# TRV_W5200.net
KiCad netlist of a schematic drawn in EAGLE
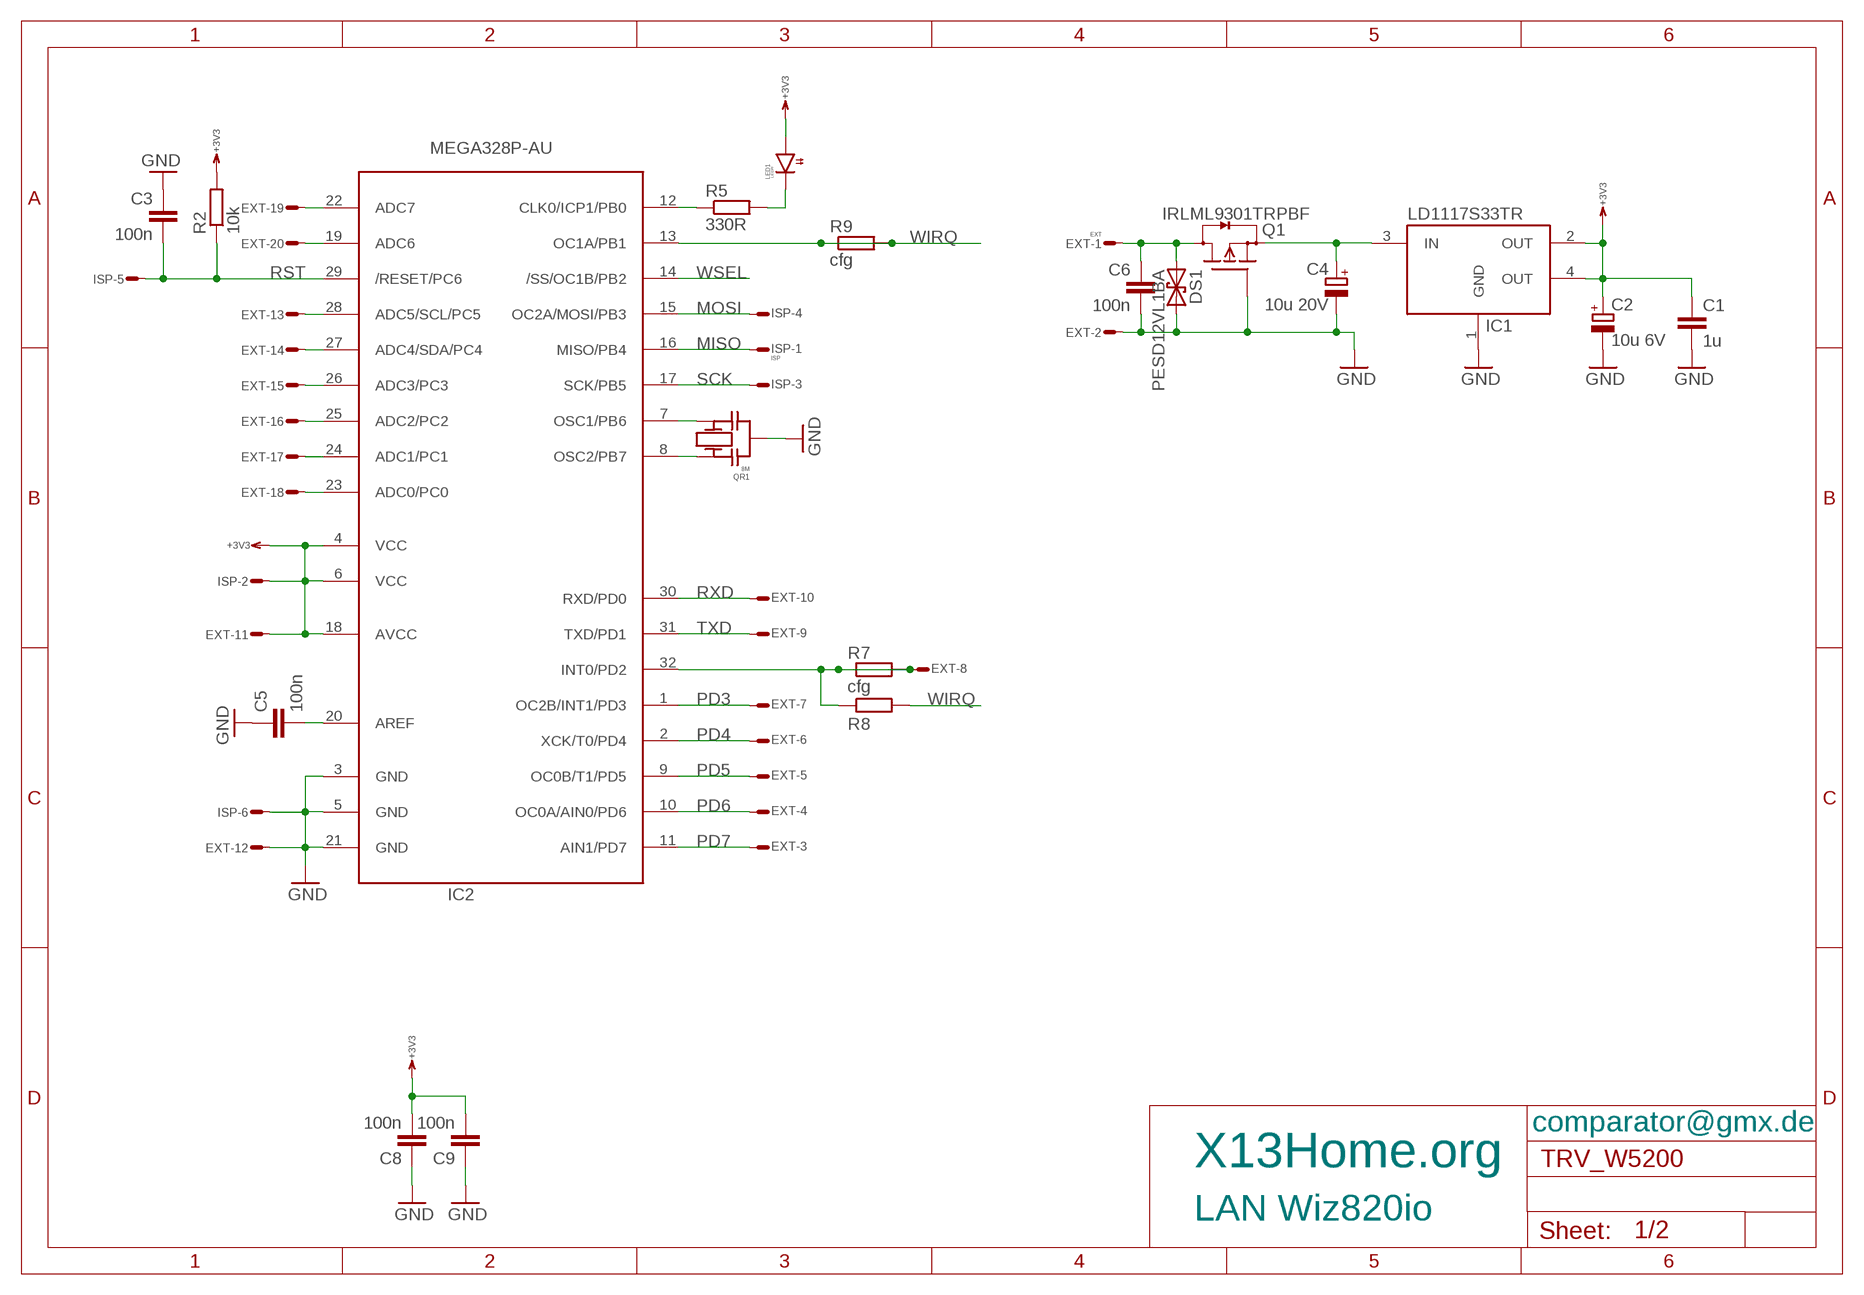
[diagram p0: schematic, sheet 1]
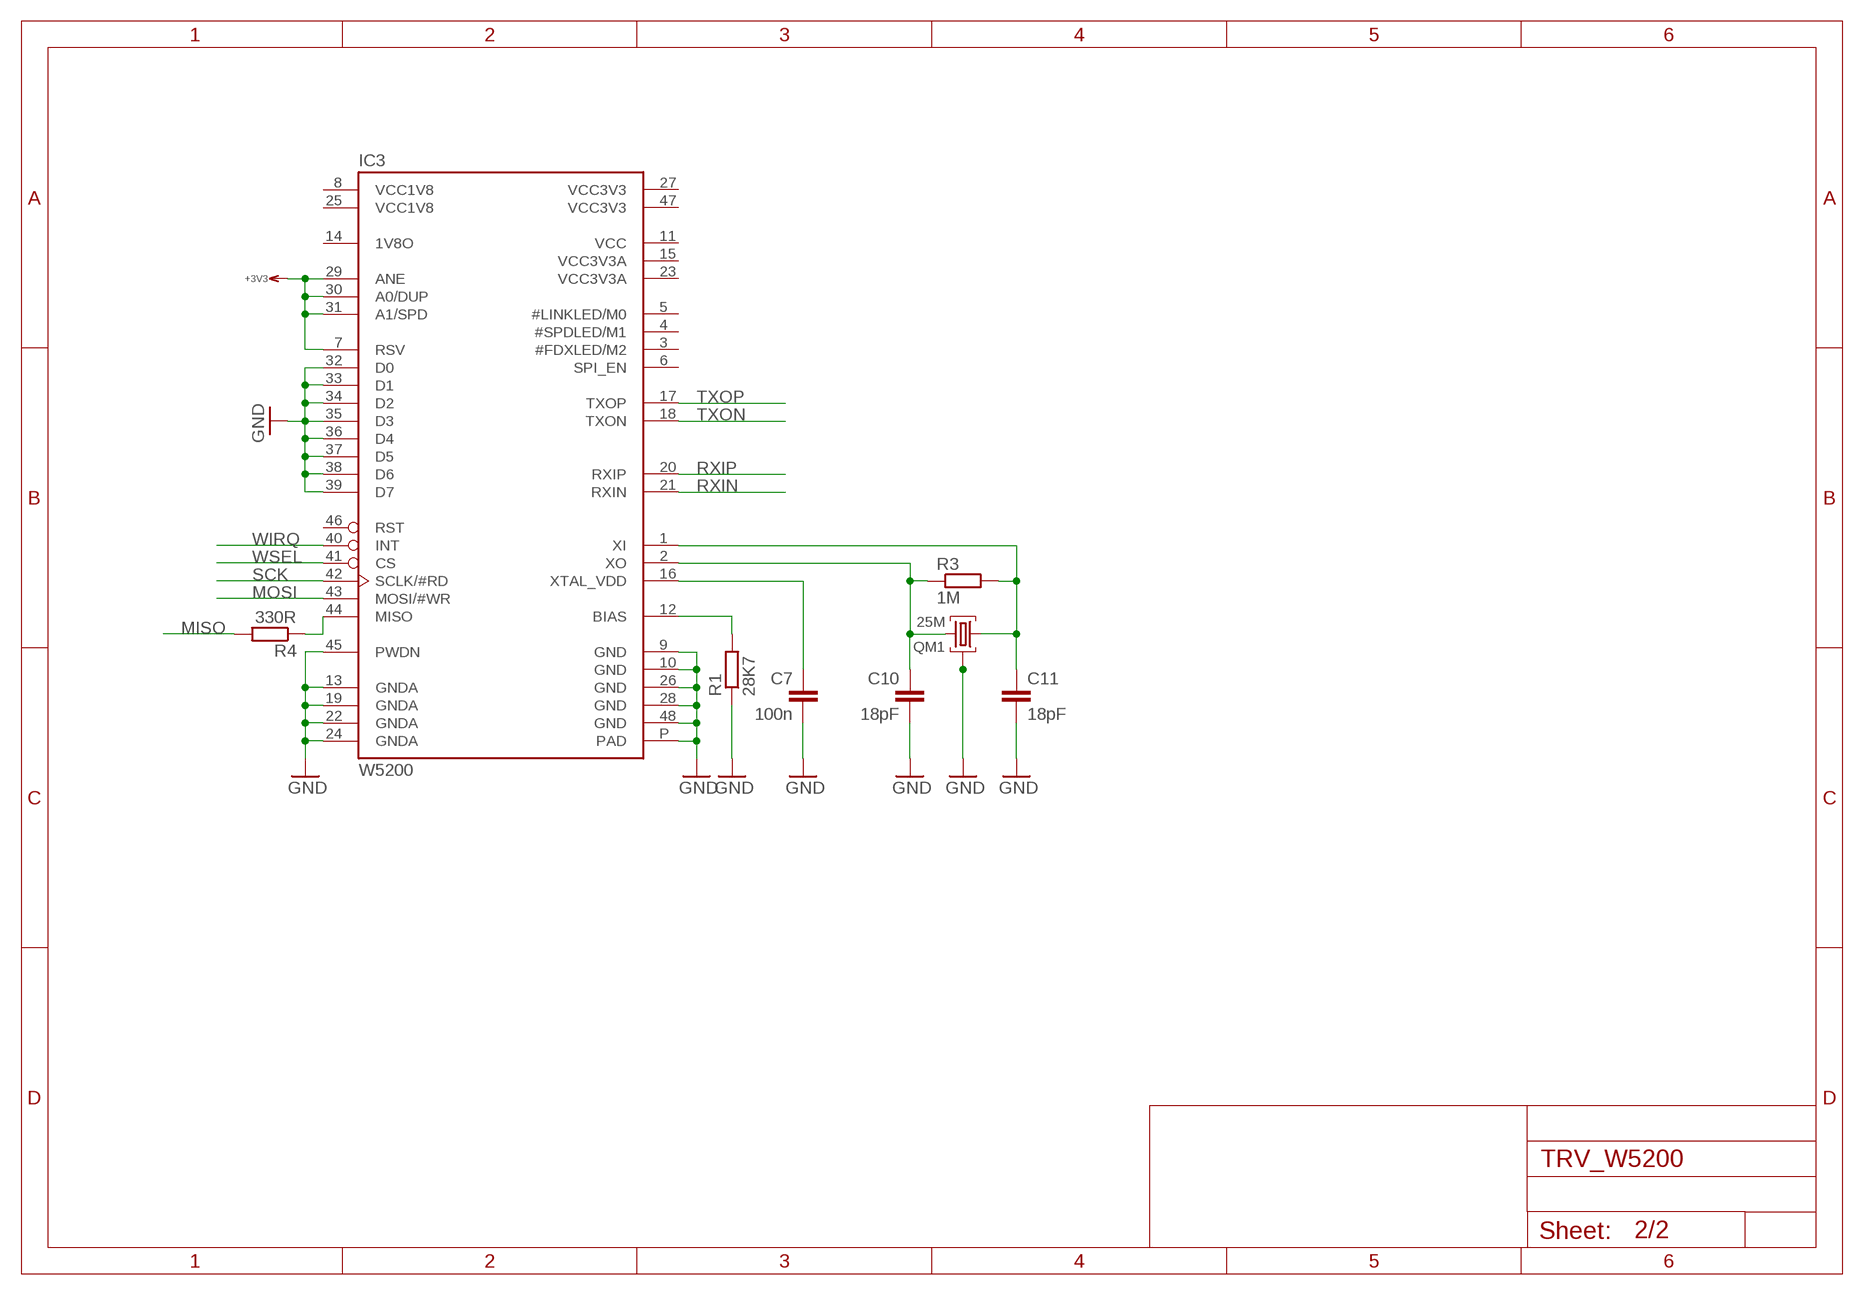
[diagram p1: schematic, sheet 2]

(export (version "E")
  (design (tool "Eeschema 10.0.6"))
  (components
    (comp (ref "C1")
      (value "1u")
      (footprint "eagle-import:0603")
      (libsource (lib "eagle-import") (part "C0603"))
    )
    (comp (ref "C2")
      (value "10u 6V")
      (footprint "eagle-import:SMC_A")
      (libsource (lib "eagle-import") (part "C_POLSMCA"))
    )
    (comp (ref "C3")
      (value "100n")
      (footprint "eagle-import:0603")
      (libsource (lib "eagle-import") (part "C0603"))
    )
    (comp (ref "C4")
      (value "10u 20V")
      (footprint "eagle-import:SMC_B")
      (libsource (lib "eagle-import") (part "C_POLSMCB"))
    )
    (comp (ref "C5")
      (value "100n")
      (footprint "eagle-import:0603")
      (libsource (lib "eagle-import") (part "C0603"))
    )
    (comp (ref "C6")
      (value "100n")
      (footprint "eagle-import:0603")
      (libsource (lib "eagle-import") (part "C0603"))
    )
    (comp (ref "C8")
      (value "100n")
      (footprint "eagle-import:0603")
      (libsource (lib "eagle-import") (part "C0603"))
    )
    (comp (ref "C9")
      (value "100n")
      (footprint "eagle-import:0603")
      (libsource (lib "eagle-import") (part "C0603"))
    )
    (comp (ref "DS1")
      (value "PESD12VL1BA")
      (footprint "eagle-import:SOD323")
      (libsource (lib "eagle-import") (part "TVS-U323"))
    )
    (comp (ref "EXT")
      (value "EXT")
      (footprint "eagle-import:ML20S")
      (libsource (lib "eagle-import") (part "ML20?ES"))
    )
    (comp (ref "IC1")
      (value "LD1117S33TR")
      (footprint "eagle-import:SOT223")
      (libsource (lib "eagle-import") (part "LDO_4P"))
    )
    (comp (ref "IC2")
      (value "MEGA328P-AU")
      (footprint "eagle-import:TQFP32-08")
      (libsource (lib "eagle-import") (part "MEGA168PA"))
    )
    (comp (ref "ISP")
      (value "ISP")
      (footprint "eagle-import:ML6S")
      (libsource (lib "eagle-import") (part "ML6ES"))
    )
    (comp (ref "LED1")
      (value "LEDR")
      (footprint "eagle-import:T1-3_4")
      (libsource (lib "eagle-import") (part "LEDT134"))
    )
    (comp (ref "Q1")
      (value "IRLML9301TRPBF")
      (footprint "eagle-import:SOT23")
      (libsource (lib "eagle-import") (part "FET-PDSOT23"))
    )
    (comp (ref "QR1")
      (value "8M")
      (footprint "eagle-import:CSTCE")
      (libsource (lib "eagle-import") (part "QRCE"))
    )
    (comp (ref "R2")
      (value "10k")
      (footprint "eagle-import:0603")
      (libsource (lib "eagle-import") (part "R0603"))
    )
    (comp (ref "R5")
      (value "330R")
      (footprint "eagle-import:0603")
      (libsource (lib "eagle-import") (part "R0603"))
    )
    (comp (ref "R7")
      (value "cfg")
      (footprint "eagle-import:0402")
      (libsource (lib "eagle-import") (part "R0402"))
    )
    (comp (ref "R8")
      (value "cfg")
      (footprint "eagle-import:0402")
      (libsource (lib "eagle-import") (part "R0402"))
    )
    (comp (ref "R9")
      (value "cfg")
      (footprint "eagle-import:0402")
      (libsource (lib "eagle-import") (part "R0402"))
    )
    (comp (ref "C7")
      (value "100n")
      (footprint "eagle-import:0603")
      (libsource (lib "eagle-import") (part "C0603"))
    )
    (comp (ref "C10")
      (value "18pF")
      (footprint "eagle-import:0603")
      (libsource (lib "eagle-import") (part "C0603"))
    )
    (comp (ref "C11")
      (value "18pF")
      (footprint "eagle-import:0603")
      (libsource (lib "eagle-import") (part "C0603"))
    )
    (comp (ref "IC3")
      (value "W5200")
      (footprint "eagle-import:QFN48")
      (libsource (lib "eagle-import") (part "W5200"))
    )
    (comp (ref "QM1")
      (value "25M")
      (footprint "eagle-import:SMD_4P_3.2X2.5")
      (libsource (lib "eagle-import") (part "QM3.2X2.5"))
    )
    (comp (ref "R1")
      (value "28K7")
      (footprint "eagle-import:0603")
      (libsource (lib "eagle-import") (part "R0603"))
    )
    (comp (ref "R3")
      (value "1M")
      (footprint "eagle-import:0603")
      (libsource (lib "eagle-import") (part "R0603"))
    )
    (comp (ref "R4")
      (value "330R")
      (footprint "eagle-import:0603")
      (libsource (lib "eagle-import") (part "R0603"))
    )
  )
  (nets
    (net (code "1") (name "+3V3") (class "Default")
      (node (ref "C1") (pin "1") (pinfunction "1_1") (pintype "passive"))
      (node (ref "C2") (pin "+") (pinfunction "+_+") (pintype "passive"))
      (node (ref "C8") (pin "2") (pinfunction "2_2") (pintype "passive"))
      (node (ref "C9") (pin "2") (pinfunction "2_2") (pintype "passive"))
      (node (ref "EXT") (pin "11") (pinfunction "S_11") (pintype "passive"))
      (node (ref "IC1") (pin "2") (pinfunction "OUT_2") (pintype "bidirectional"))
      (node (ref "IC1") (pin "4") (pinfunction "OUT_4") (pintype "bidirectional"))
      (node (ref "IC2") (pin "18") (pinfunction "AVCC_18") (pintype "bidirectional"))
      (node (ref "IC2") (pin "4") (pinfunction "VCC_4") (pintype "bidirectional"))
      (node (ref "IC2") (pin "6") (pinfunction "VCC_6") (pintype "bidirectional"))
      (node (ref "IC3") (pin "29") (pinfunction "ANE_29") (pintype "input"))
      (node (ref "IC3") (pin "30") (pinfunction "A0/DUP_30") (pintype "input"))
      (node (ref "IC3") (pin "31") (pinfunction "A1/SPD_31") (pintype "input"))
      (node (ref "IC3") (pin "7") (pinfunction "RSV_7") (pintype "input"))
      (node (ref "ISP") (pin "2") (pinfunction "S_2") (pintype "passive"))
      (node (ref "LED1") (pin "A") (pinfunction "A_A") (pintype "bidirectional"))
      (node (ref "R2") (pin "2") (pinfunction "2_2") (pintype "passive"))
    )
    (net (code "2") (name "GND") (class "Default")
      (node (ref "C1") (pin "2") (pinfunction "2_2") (pintype "passive"))
      (node (ref "C10") (pin "2") (pinfunction "2_2") (pintype "passive"))
      (node (ref "C11") (pin "2") (pinfunction "2_2") (pintype "passive"))
      (node (ref "C2") (pin "-") (pinfunction "-_-") (pintype "passive"))
      (node (ref "C3") (pin "1") (pinfunction "1_1") (pintype "passive"))
      (node (ref "C4") (pin "-") (pinfunction "-_-") (pintype "passive"))
      (node (ref "C5") (pin "1") (pinfunction "1_1") (pintype "passive"))
      (node (ref "C6") (pin "2") (pinfunction "2_2") (pintype "passive"))
      (node (ref "C7") (pin "2") (pinfunction "2_2") (pintype "passive"))
      (node (ref "C8") (pin "1") (pinfunction "1_1") (pintype "passive"))
      (node (ref "C9") (pin "1") (pinfunction "1_1") (pintype "passive"))
      (node (ref "DS1") (pin "C") (pinfunction "2_C") (pintype "passive"))
      (node (ref "EXT") (pin "12") (pinfunction "S_12") (pintype "passive"))
      (node (ref "EXT") (pin "2") (pinfunction "S_2") (pintype "passive"))
      (node (ref "IC1") (pin "1") (pinfunction "GND_1") (pintype "bidirectional"))
      (node (ref "IC2") (pin "21") (pinfunction "GND_21") (pintype "bidirectional"))
      (node (ref "IC2") (pin "3") (pinfunction "GND_3") (pintype "bidirectional"))
      (node (ref "IC2") (pin "5") (pinfunction "GND_5") (pintype "bidirectional"))
      (node (ref "IC3") (pin "10") (pinfunction "GND_10") (pintype "bidirectional"))
      (node (ref "IC3") (pin "13") (pinfunction "GNDA_13") (pintype "bidirectional"))
      (node (ref "IC3") (pin "19") (pinfunction "GNDA_19") (pintype "bidirectional"))
      (node (ref "IC3") (pin "22") (pinfunction "GNDA_22") (pintype "bidirectional"))
      (node (ref "IC3") (pin "24") (pinfunction "GNDA_24") (pintype "bidirectional"))
      (node (ref "IC3") (pin "26") (pinfunction "GND_26") (pintype "bidirectional"))
      (node (ref "IC3") (pin "28") (pinfunction "GND_28") (pintype "bidirectional"))
      (node (ref "IC3") (pin "32") (pinfunction "D0_32") (pintype "bidirectional"))
      (node (ref "IC3") (pin "33") (pinfunction "D1_33") (pintype "bidirectional"))
      (node (ref "IC3") (pin "34") (pinfunction "D2_34") (pintype "bidirectional"))
      (node (ref "IC3") (pin "35") (pinfunction "D3_35") (pintype "bidirectional"))
      (node (ref "IC3") (pin "36") (pinfunction "D4_36") (pintype "bidirectional"))
      (node (ref "IC3") (pin "37") (pinfunction "D5_37") (pintype "bidirectional"))
      (node (ref "IC3") (pin "38") (pinfunction "D6_38") (pintype "bidirectional"))
      (node (ref "IC3") (pin "39") (pinfunction "D7_39") (pintype "bidirectional"))
      (node (ref "IC3") (pin "45") (pinfunction "PWDN_45") (pintype "input"))
      (node (ref "IC3") (pin "48") (pinfunction "GND_48") (pintype "bidirectional"))
      (node (ref "IC3") (pin "9") (pinfunction "GND_9") (pintype "bidirectional"))
      (node (ref "IC3") (pin "P") (pinfunction "PAD_P") (pintype "bidirectional"))
      (node (ref "ISP") (pin "6") (pinfunction "S_6") (pintype "passive"))
      (node (ref "Q1") (pin "1") (pinfunction "G_1") (pintype "passive"))
      (node (ref "QM1") (pin "2") (pinfunction "M1_2") (pintype "passive"))
      (node (ref "QM1") (pin "4") (pinfunction "M2_4") (pintype "passive"))
      (node (ref "QR1") (pin "G") (pinfunction "M_G") (pintype "passive"))
      (node (ref "R1") (pin "1") (pinfunction "1_1") (pintype "passive"))
    )
    (net (code "3") (name "MISO") (class "Default")
      (node (ref "IC2") (pin "16") (pinfunction "MISO/PB4_16") (pintype "bidirectional"))
      (node (ref "ISP") (pin "1") (pinfunction "S_1") (pintype "passive"))
      (node (ref "R4") (pin "2") (pinfunction "2_2") (pintype "passive"))
    )
    (net (code "4") (name "MOSI") (class "Default")
      (node (ref "IC2") (pin "15") (pinfunction "OC2A/MOSI/PB3_15") (pintype "bidirectional"))
      (node (ref "IC3") (pin "43") (pinfunction "MOSI/#WR_43") (pintype "input"))
      (node (ref "ISP") (pin "4") (pinfunction "S_4") (pintype "passive"))
    )
    (net (code "5") (name "Net-(DS1-1)") (class "Default")
      (node (ref "C6") (pin "1") (pinfunction "1_1") (pintype "passive"))
      (node (ref "DS1") (pin "A") (pinfunction "1_A") (pintype "passive"))
      (node (ref "EXT") (pin "1") (pinfunction "S_1") (pintype "passive"))
      (node (ref "Q1") (pin "3") (pinfunction "D_3") (pintype "passive"))
    )
    (net (code "6") (name "Net-(EXTE-S)") (class "Default")
      (node (ref "EXT") (pin "13") (pinfunction "S_13") (pintype "passive"))
      (node (ref "IC2") (pin "28") (pinfunction "ADC5/SCL/PC5_28") (pintype "bidirectional"))
    )
    (net (code "7") (name "Net-(EXTF-S)") (class "Default")
      (node (ref "EXT") (pin "14") (pinfunction "S_14") (pintype "passive"))
      (node (ref "IC2") (pin "27") (pinfunction "ADC4/SDA/PC4_27") (pintype "bidirectional"))
    )
    (net (code "8") (name "Net-(EXTG-S)") (class "Default")
      (node (ref "EXT") (pin "15") (pinfunction "S_15") (pintype "passive"))
      (node (ref "IC2") (pin "26") (pinfunction "ADC3/PC3_26") (pintype "bidirectional"))
    )
    (net (code "9") (name "Net-(EXTH-S)") (class "Default")
      (node (ref "EXT") (pin "16") (pinfunction "S_16") (pintype "passive"))
      (node (ref "IC2") (pin "25") (pinfunction "ADC2/PC2_25") (pintype "bidirectional"))
    )
    (net (code "10") (name "Net-(EXTI-S)") (class "Default")
      (node (ref "EXT") (pin "17") (pinfunction "S_17") (pintype "passive"))
      (node (ref "IC2") (pin "24") (pinfunction "ADC1/PC1_24") (pintype "bidirectional"))
    )
    (net (code "11") (name "Net-(EXTJ-S)") (class "Default")
      (node (ref "EXT") (pin "18") (pinfunction "S_18") (pintype "passive"))
      (node (ref "IC2") (pin "23") (pinfunction "ADC0/PC0_23") (pintype "bidirectional"))
    )
    (net (code "12") (name "Net-(EXTK-S)") (class "Default")
      (node (ref "EXT") (pin "19") (pinfunction "S_19") (pintype "passive"))
      (node (ref "IC2") (pin "22") (pinfunction "ADC7_22") (pintype "bidirectional"))
    )
    (net (code "13") (name "Net-(EXTM-S)") (class "Default")
      (node (ref "EXT") (pin "20") (pinfunction "S_20") (pintype "passive"))
      (node (ref "IC2") (pin "19") (pinfunction "ADC6_19") (pintype "bidirectional"))
    )
    (net (code "14") (name "Net-(EXTS-S)") (class "Default")
      (node (ref "EXT") (pin "8") (pinfunction "S_8") (pintype "passive"))
      (node (ref "IC2") (pin "32") (pinfunction "INT0/PD2_32") (pintype "bidirectional"))
      (node (ref "R7") (pin "1") (pinfunction "1_1") (pintype "passive"))
      (node (ref "R7") (pin "2") (pinfunction "2_2") (pintype "passive"))
      (node (ref "R8") (pin "1") (pinfunction "1_1") (pintype "passive"))
    )
    (net (code "15") (name "Net-(IC1-IN)") (class "Default")
      (node (ref "C4") (pin "+") (pinfunction "+_+") (pintype "passive"))
      (node (ref "IC1") (pin "3") (pinfunction "IN_3") (pintype "bidirectional"))
      (node (ref "Q1") (pin "2") (pinfunction "S_2") (pintype "passive"))
    )
    (net (code "16") (name "Net-(IC2-AREF)") (class "Default")
      (node (ref "C5") (pin "2") (pinfunction "2_2") (pintype "passive"))
      (node (ref "IC2") (pin "20") (pinfunction "AREF_20") (pintype "bidirectional"))
    )
    (net (code "17") (name "Net-(IC2-CLK0{slash}ICP1{slash}PB0)") (class "Default")
      (node (ref "IC2") (pin "12") (pinfunction "CLK0/ICP1/PB0_12") (pintype "bidirectional"))
      (node (ref "R5") (pin "1") (pinfunction "1_1") (pintype "passive"))
    )
    (net (code "18") (name "Net-(IC2-OSC1{slash}PB6)") (class "Default")
      (node (ref "IC2") (pin "7") (pinfunction "OSC1/PB6_7") (pintype "bidirectional"))
      (node (ref "QR1") (pin "B") (pinfunction "2_B") (pintype "passive"))
    )
    (net (code "19") (name "Net-(IC2-OSC2{slash}PB7)") (class "Default")
      (node (ref "IC2") (pin "8") (pinfunction "OSC2/PB7_8") (pintype "bidirectional"))
      (node (ref "QR1") (pin "A") (pinfunction "1_A") (pintype "passive"))
    )
    (net (code "20") (name "Net-(IC3-BIAS)") (class "Default")
      (node (ref "IC3") (pin "12") (pinfunction "BIAS_12") (pintype "output"))
      (node (ref "R1") (pin "2") (pinfunction "2_2") (pintype "passive"))
    )
    (net (code "21") (name "Net-(IC3-MISO)") (class "Default")
      (node (ref "IC3") (pin "44") (pinfunction "MISO_44") (pintype "output"))
      (node (ref "R4") (pin "1") (pinfunction "1_1") (pintype "passive"))
    )
    (net (code "22") (name "Net-(IC3-XI)") (class "Default")
      (node (ref "C11") (pin "1") (pinfunction "1_1") (pintype "passive"))
      (node (ref "IC3") (pin "1") (pinfunction "XI_1") (pintype "input"))
      (node (ref "QM1") (pin "1") (pinfunction "1_1") (pintype "passive"))
      (node (ref "R3") (pin "2") (pinfunction "2_2") (pintype "passive"))
    )
    (net (code "23") (name "Net-(IC3-XO)") (class "Default")
      (node (ref "C10") (pin "1") (pinfunction "1_1") (pintype "passive"))
      (node (ref "IC3") (pin "2") (pinfunction "XO_2") (pintype "output"))
      (node (ref "QM1") (pin "3") (pinfunction "2_3") (pintype "passive"))
      (node (ref "R3") (pin "1") (pinfunction "1_1") (pintype "passive"))
    )
    (net (code "24") (name "Net-(IC3-XTAL_VDD)") (class "Default")
      (node (ref "C7") (pin "1") (pinfunction "1_1") (pintype "passive"))
      (node (ref "IC3") (pin "16") (pinfunction "XTAL_VDD_16") (pintype "input"))
    )
    (net (code "25") (name "Net-(LED1-PadC)") (class "Default")
      (node (ref "LED1") (pin "C") (pinfunction "C_C") (pintype "bidirectional"))
      (node (ref "R5") (pin "2") (pinfunction "2_2") (pintype "passive"))
    )
    (net (code "26") (name "PD3") (class "Default")
      (node (ref "EXT") (pin "7") (pinfunction "S_7") (pintype "passive"))
      (node (ref "IC2") (pin "1") (pinfunction "OC2B/INT1/PD3_1") (pintype "bidirectional"))
    )
    (net (code "27") (name "PD4") (class "Default")
      (node (ref "EXT") (pin "6") (pinfunction "S_6") (pintype "passive"))
      (node (ref "IC2") (pin "2") (pinfunction "XCK/T0/PD4_2") (pintype "bidirectional"))
    )
    (net (code "28") (name "PD5") (class "Default")
      (node (ref "EXT") (pin "5") (pinfunction "S_5") (pintype "passive"))
      (node (ref "IC2") (pin "9") (pinfunction "OC0B/T1/PD5_9") (pintype "bidirectional"))
    )
    (net (code "29") (name "PD6") (class "Default")
      (node (ref "EXT") (pin "4") (pinfunction "S_4") (pintype "passive"))
      (node (ref "IC2") (pin "10") (pinfunction "OC0A/AIN0/PD6_10") (pintype "bidirectional"))
    )
    (net (code "30") (name "PD7") (class "Default")
      (node (ref "EXT") (pin "3") (pinfunction "S_3") (pintype "passive"))
      (node (ref "IC2") (pin "11") (pinfunction "AIN1/PD7_11") (pintype "bidirectional"))
    )
    (net (code "31") (name "RST") (class "Default")
      (node (ref "C3") (pin "2") (pinfunction "2_2") (pintype "passive"))
      (node (ref "IC2") (pin "29") (pinfunction "/RESET/PC6_29") (pintype "bidirectional"))
      (node (ref "ISP") (pin "5") (pinfunction "S_5") (pintype "passive"))
      (node (ref "R2") (pin "1") (pinfunction "1_1") (pintype "passive"))
    )
    (net (code "32") (name "RXD") (class "Default")
      (node (ref "EXT") (pin "10") (pinfunction "S_10") (pintype "passive"))
      (node (ref "IC2") (pin "30") (pinfunction "RXD/PD0_30") (pintype "bidirectional"))
    )
    (net (code "33") (name "RXIN") (class "Default")
      (node (ref "IC3") (pin "21") (pinfunction "RXIN_21") (pintype "input"))
    )
    (net (code "34") (name "RXIP") (class "Default")
      (node (ref "IC3") (pin "20") (pinfunction "RXIP_20") (pintype "input"))
    )
    (net (code "35") (name "SCK") (class "Default")
      (node (ref "IC2") (pin "17") (pinfunction "SCK/PB5_17") (pintype "bidirectional"))
      (node (ref "IC3") (pin "42") (pinfunction "SCLK/#RD_42") (pintype "bidirectional"))
      (node (ref "ISP") (pin "3") (pinfunction "S_3") (pintype "passive"))
    )
    (net (code "36") (name "TXD") (class "Default")
      (node (ref "EXT") (pin "9") (pinfunction "S_9") (pintype "passive"))
      (node (ref "IC2") (pin "31") (pinfunction "TXD/PD1_31") (pintype "bidirectional"))
    )
    (net (code "37") (name "TXON") (class "Default")
      (node (ref "IC3") (pin "18") (pinfunction "TXON_18") (pintype "output"))
    )
    (net (code "38") (name "TXOP") (class "Default")
      (node (ref "IC3") (pin "17") (pinfunction "TXOP_17") (pintype "output"))
    )
    (net (code "39") (name "WIRQ") (class "Default")
      (node (ref "IC2") (pin "13") (pinfunction "OC1A/PB1_13") (pintype "bidirectional"))
      (node (ref "IC3") (pin "40") (pinfunction "INT_40") (pintype "output"))
      (node (ref "R8") (pin "2") (pinfunction "2_2") (pintype "passive"))
      (node (ref "R9") (pin "1") (pinfunction "1_1") (pintype "passive"))
      (node (ref "R9") (pin "2") (pinfunction "2_2") (pintype "passive"))
    )
    (net (code "40") (name "WSEL") (class "Default")
      (node (ref "IC2") (pin "14") (pinfunction "/SS/OC1B/PB2_14") (pintype "bidirectional"))
      (node (ref "IC3") (pin "41") (pinfunction "CS_41") (pintype "input"))
    )
    (net (code "41") (name "unconnected-(IC3-#FDXLED{slash}M2-Pad3)") (class "Default")
      (node (ref "IC3") (pin "3") (pinfunction "#FDXLED/M2_3") (pintype "bidirectional"))
    )
    (net (code "42") (name "unconnected-(IC3-#LINKLED{slash}M0-Pad5)") (class "Default")
      (node (ref "IC3") (pin "5") (pinfunction "#LINKLED/M0_5") (pintype "bidirectional"))
    )
    (net (code "43") (name "unconnected-(IC3-#SPDLED{slash}M1-Pad4)") (class "Default")
      (node (ref "IC3") (pin "4") (pinfunction "#SPDLED/M1_4") (pintype "bidirectional"))
    )
    (net (code "44") (name "unconnected-(IC3-1V8O-Pad14)") (class "Default")
      (node (ref "IC3") (pin "14") (pinfunction "1V8O_14") (pintype "bidirectional"))
    )
    (net (code "45") (name "unconnected-(IC3-RST-Pad46)") (class "Default")
      (node (ref "IC3") (pin "46") (pinfunction "RST_46") (pintype "input"))
    )
    (net (code "46") (name "unconnected-(IC3-SPI_EN-Pad6)") (class "Default")
      (node (ref "IC3") (pin "6") (pinfunction "SPI_EN_6") (pintype "input"))
    )
    (net (code "47") (name "unconnected-(IC3-VCC-Pad11)") (class "Default")
      (node (ref "IC3") (pin "11") (pinfunction "VCC_11") (pintype "bidirectional"))
    )
    (net (code "48") (name "unconnected-(IC3-VCC1V8-Pad8)") (class "Default")
      (node (ref "IC3") (pin "8") (pinfunction "VCC1V8_8") (pintype "bidirectional"))
    )
    (net (code "49") (name "unconnected-(IC3-VCC1V8-Pad25)") (class "Default")
      (node (ref "IC3") (pin "25") (pinfunction "VCC1V8_25") (pintype "bidirectional"))
    )
    (net (code "50") (name "unconnected-(IC3-VCC3V3-Pad27)") (class "Default")
      (node (ref "IC3") (pin "27") (pinfunction "VCC3V3_27") (pintype "bidirectional"))
    )
    (net (code "51") (name "unconnected-(IC3-VCC3V3-Pad47)") (class "Default")
      (node (ref "IC3") (pin "47") (pinfunction "VCC3V3_47") (pintype "bidirectional"))
    )
    (net (code "52") (name "unconnected-(IC3-VCC3V3A-Pad15)") (class "Default")
      (node (ref "IC3") (pin "15") (pinfunction "VCC3V3A_15") (pintype "bidirectional"))
    )
    (net (code "53") (name "unconnected-(IC3-VCC3V3A-Pad23)") (class "Default")
      (node (ref "IC3") (pin "23") (pinfunction "VCC3V3A_23") (pintype "bidirectional"))
    )
  )
)
